# PCA9548A.net
KiCad netlist of a schematic drawn in EAGLE
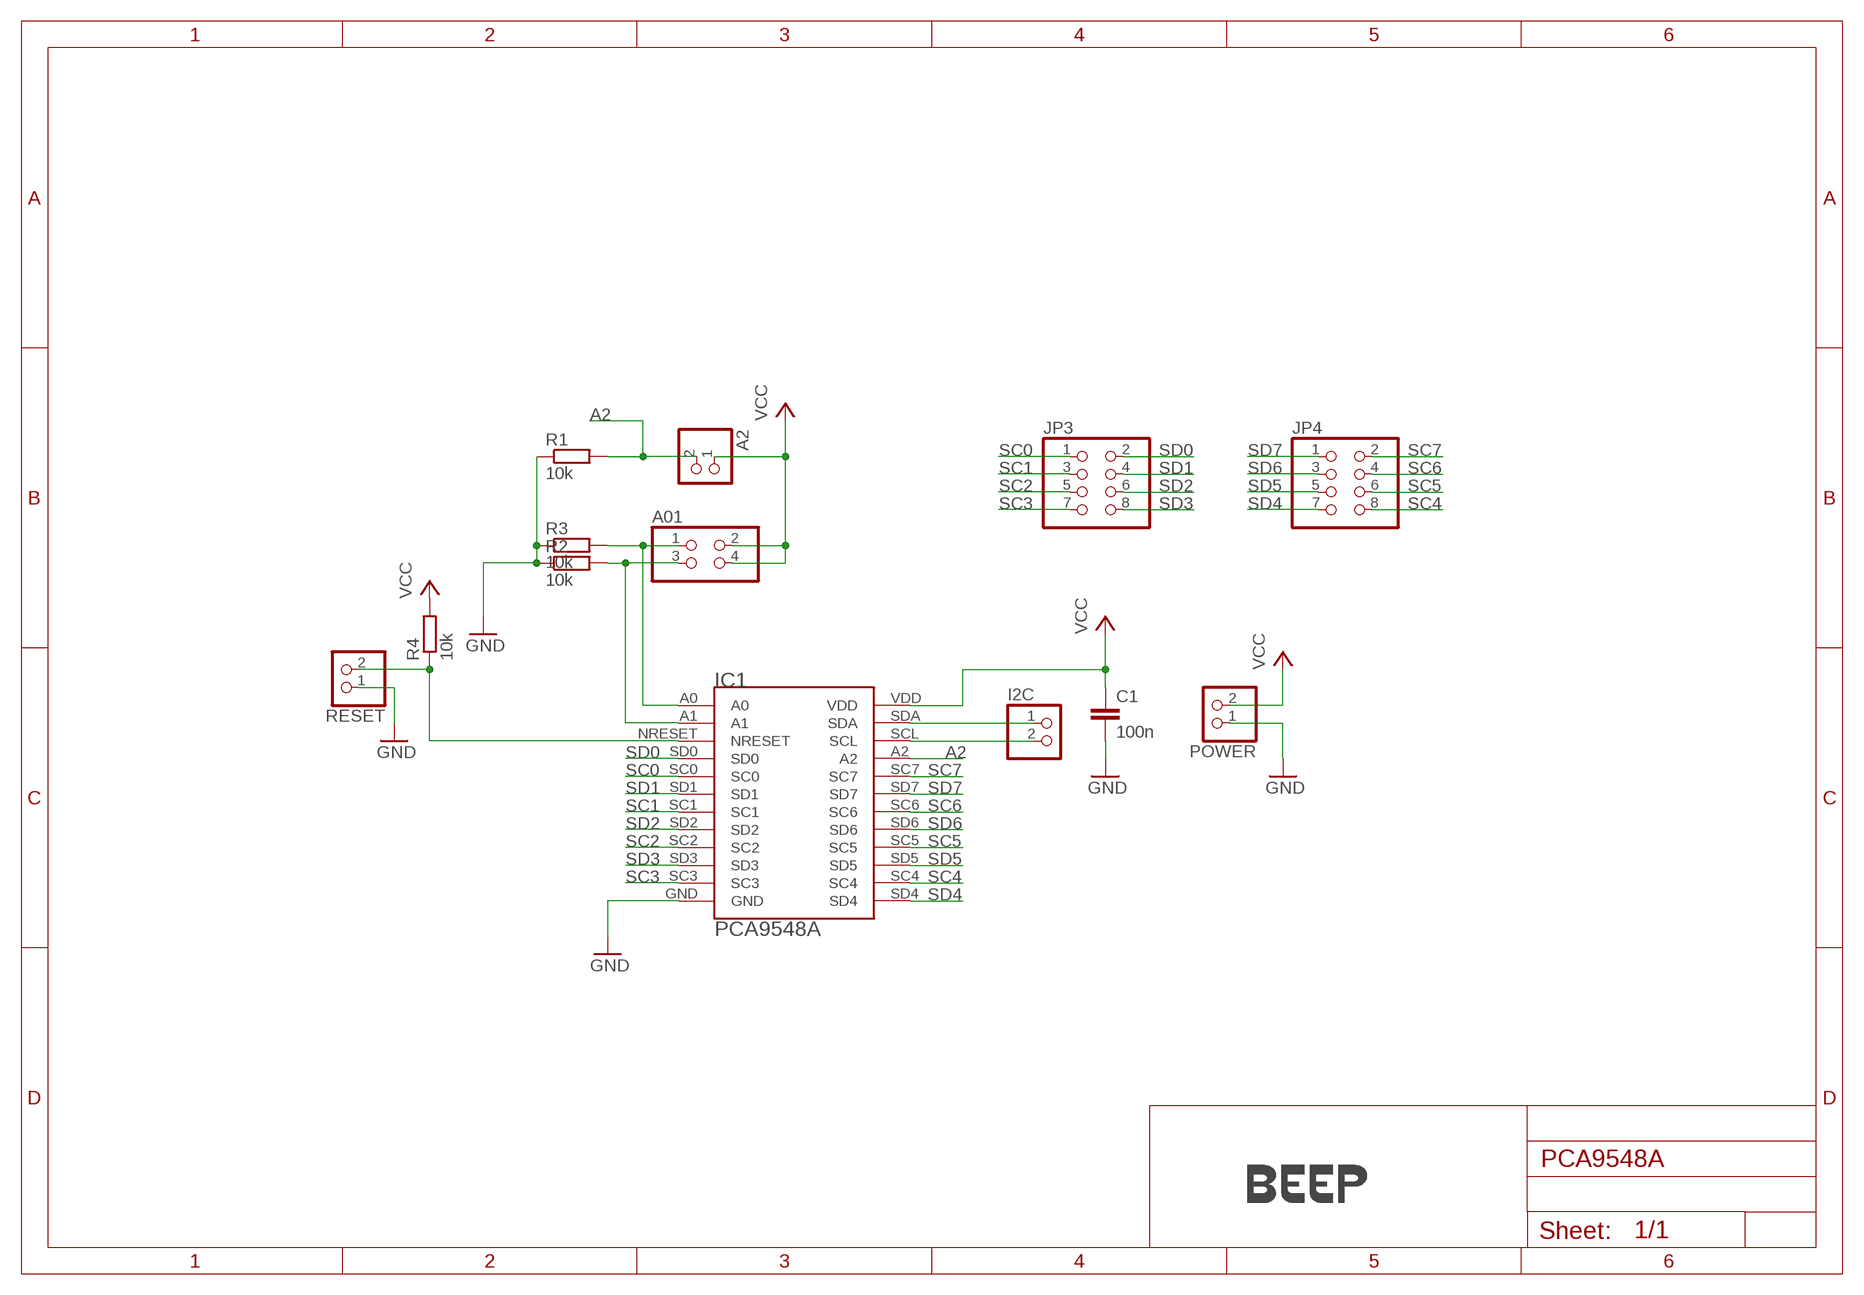
[diagram p0: schematic, sheet 1]

(export (version "E")
  (design (tool "Eeschema 10.0.6"))
  (components
    (comp (ref "A01")
      (value "PINHD-2X2")
      (footprint "eagle-import:2X02")
      (libsource (lib "eagle-import") (part "PINHD-2X2"))
    )
    (comp (ref "A2")
      (value "PINHD-1X2")
      (footprint "eagle-import:1X02")
      (libsource (lib "eagle-import") (part "PINHD-1X2"))
    )
    (comp (ref "C1")
      (value "100n")
      (footprint "eagle-import:C0805")
      (libsource (lib "eagle-import") (part "C-EUC0805"))
    )
    (comp (ref "I2C")
      (value "PINHD-1X2")
      (footprint "eagle-import:1X02")
      (libsource (lib "eagle-import") (part "PINHD-1X2"))
    )
    (comp (ref "IC1")
      (value "PCA9548A")
      (footprint "eagle-import:TSSOP24")
      (libsource (lib "eagle-import") (part "PCA9548A"))
    )
    (comp (ref "JP3")
      (value "PINHD-2X4")
      (footprint "eagle-import:2X04")
      (libsource (lib "eagle-import") (part "PINHD-2X4"))
    )
    (comp (ref "JP4")
      (value "PINHD-2X4")
      (footprint "eagle-import:2X04")
      (libsource (lib "eagle-import") (part "PINHD-2X4"))
    )
    (comp (ref "POWER")
      (value "PINHD-1X2")
      (footprint "eagle-import:1X02")
      (libsource (lib "eagle-import") (part "PINHD-1X2"))
    )
    (comp (ref "R1")
      (value "10k")
      (footprint "eagle-import:0207_7")
      (libsource (lib "eagle-import") (part "R-EU_0207/7"))
    )
    (comp (ref "R2")
      (value "10k")
      (footprint "eagle-import:0207_7")
      (libsource (lib "eagle-import") (part "R-EU_0207/7"))
    )
    (comp (ref "R3")
      (value "10k")
      (footprint "eagle-import:0207_7")
      (libsource (lib "eagle-import") (part "R-EU_0207/7"))
    )
    (comp (ref "R4")
      (value "10k")
      (footprint "eagle-import:M0805")
      (libsource (lib "eagle-import") (part "R-EU_M0805"))
    )
    (comp (ref "RESET")
      (value "PINHD-1X2")
      (footprint "eagle-import:1X02")
      (libsource (lib "eagle-import") (part "PINHD-1X2"))
    )
    (comp (ref "U$1")
      (value "LOGO-COPPER4")
      (footprint "eagle-import:COPPER4")
      (libsource (lib "eagle-import") (part "LOGO-COPPER4"))
    )
  )
  (nets
    (net (code "1") (name "/A2") (class "Default")
      (node (ref "A2") (pin "2") (pinfunction "2_2") (pintype "passive"))
      (node (ref "IC1") (pin "A2") (pinfunction "A2_A2") (pintype "bidirectional"))
      (node (ref "R1") (pin "2") (pinfunction "2_2") (pintype "passive"))
    )
    (net (code "2") (name "/SC0") (class "Default")
      (node (ref "IC1") (pin "SC0") (pinfunction "SC0_SC0") (pintype "bidirectional"))
      (node (ref "JP3") (pin "1") (pinfunction "1_1") (pintype "passive"))
    )
    (net (code "3") (name "/SC1") (class "Default")
      (node (ref "IC1") (pin "SC1") (pinfunction "SC1_SC1") (pintype "bidirectional"))
      (node (ref "JP3") (pin "3") (pinfunction "3_3") (pintype "passive"))
    )
    (net (code "4") (name "/SC2") (class "Default")
      (node (ref "IC1") (pin "SC2") (pinfunction "SC2_SC2") (pintype "bidirectional"))
      (node (ref "JP3") (pin "5") (pinfunction "5_5") (pintype "passive"))
    )
    (net (code "5") (name "/SC3") (class "Default")
      (node (ref "IC1") (pin "SC3") (pinfunction "SC3_SC3") (pintype "bidirectional"))
      (node (ref "JP3") (pin "7") (pinfunction "7_7") (pintype "passive"))
    )
    (net (code "6") (name "/SC4") (class "Default")
      (node (ref "IC1") (pin "SC4") (pinfunction "SC4_SC4") (pintype "bidirectional"))
      (node (ref "JP4") (pin "8") (pinfunction "8_8") (pintype "passive"))
    )
    (net (code "7") (name "/SC5") (class "Default")
      (node (ref "IC1") (pin "SC5") (pinfunction "SC5_SC5") (pintype "bidirectional"))
      (node (ref "JP4") (pin "6") (pinfunction "6_6") (pintype "passive"))
    )
    (net (code "8") (name "/SC6") (class "Default")
      (node (ref "IC1") (pin "SC6") (pinfunction "SC6_SC6") (pintype "bidirectional"))
      (node (ref "JP4") (pin "4") (pinfunction "4_4") (pintype "passive"))
    )
    (net (code "9") (name "/SC7") (class "Default")
      (node (ref "IC1") (pin "SC7") (pinfunction "SC7_SC7") (pintype "bidirectional"))
      (node (ref "JP4") (pin "2") (pinfunction "2_2") (pintype "passive"))
    )
    (net (code "10") (name "/SD0") (class "Default")
      (node (ref "IC1") (pin "SD0") (pinfunction "SD0_SD0") (pintype "bidirectional"))
      (node (ref "JP3") (pin "2") (pinfunction "2_2") (pintype "passive"))
    )
    (net (code "11") (name "/SD1") (class "Default")
      (node (ref "IC1") (pin "SD1") (pinfunction "SD1_SD1") (pintype "bidirectional"))
      (node (ref "JP3") (pin "4") (pinfunction "4_4") (pintype "passive"))
    )
    (net (code "12") (name "/SD2") (class "Default")
      (node (ref "IC1") (pin "SD2") (pinfunction "SD2_SD2") (pintype "bidirectional"))
      (node (ref "JP3") (pin "6") (pinfunction "6_6") (pintype "passive"))
    )
    (net (code "13") (name "/SD3") (class "Default")
      (node (ref "IC1") (pin "SD3") (pinfunction "SD3_SD3") (pintype "bidirectional"))
      (node (ref "JP3") (pin "8") (pinfunction "8_8") (pintype "passive"))
    )
    (net (code "14") (name "/SD4") (class "Default")
      (node (ref "IC1") (pin "SD4") (pinfunction "SD4_SD4") (pintype "bidirectional"))
      (node (ref "JP4") (pin "7") (pinfunction "7_7") (pintype "passive"))
    )
    (net (code "15") (name "/SD5") (class "Default")
      (node (ref "IC1") (pin "SD5") (pinfunction "SD5_SD5") (pintype "bidirectional"))
      (node (ref "JP4") (pin "5") (pinfunction "5_5") (pintype "passive"))
    )
    (net (code "16") (name "/SD6") (class "Default")
      (node (ref "IC1") (pin "SD6") (pinfunction "SD6_SD6") (pintype "bidirectional"))
      (node (ref "JP4") (pin "3") (pinfunction "3_3") (pintype "passive"))
    )
    (net (code "17") (name "/SD7") (class "Default")
      (node (ref "IC1") (pin "SD7") (pinfunction "SD7_SD7") (pintype "bidirectional"))
      (node (ref "JP4") (pin "1") (pinfunction "1_1") (pintype "passive"))
    )
    (net (code "18") (name "GND") (class "Default")
      (node (ref "C1") (pin "2") (pinfunction "2_2") (pintype "passive"))
      (node (ref "IC1") (pin "GND") (pinfunction "GND_GND") (pintype "power_in"))
      (node (ref "POWER") (pin "1") (pinfunction "1_1") (pintype "passive"))
      (node (ref "R1") (pin "1") (pinfunction "1_1") (pintype "passive"))
      (node (ref "R2") (pin "1") (pinfunction "1_1") (pintype "passive"))
      (node (ref "R3") (pin "1") (pinfunction "1_1") (pintype "passive"))
      (node (ref "RESET") (pin "1") (pinfunction "1_1") (pintype "passive"))
    )
    (net (code "19") (name "Net-(A01-Pad1)") (class "Default")
      (node (ref "A01") (pin "1") (pinfunction "1_1") (pintype "passive"))
      (node (ref "IC1") (pin "A0") (pinfunction "A0_A0") (pintype "input"))
      (node (ref "R3") (pin "2") (pinfunction "2_2") (pintype "passive"))
    )
    (net (code "20") (name "Net-(A01-Pad3)") (class "Default")
      (node (ref "A01") (pin "3") (pinfunction "3_3") (pintype "passive"))
      (node (ref "IC1") (pin "A1") (pinfunction "A1_A1") (pintype "input"))
      (node (ref "R2") (pin "2") (pinfunction "2_2") (pintype "passive"))
    )
    (net (code "21") (name "Net-(I2C-Pad1)") (class "Default")
      (node (ref "I2C") (pin "1") (pinfunction "1_1") (pintype "passive"))
      (node (ref "IC1") (pin "SDA") (pinfunction "SDA_SDA") (pintype "bidirectional"))
    )
    (net (code "22") (name "Net-(I2C-Pad2)") (class "Default")
      (node (ref "I2C") (pin "2") (pinfunction "2_2") (pintype "passive"))
      (node (ref "IC1") (pin "SCL") (pinfunction "SCL_SCL") (pintype "bidirectional"))
    )
    (net (code "23") (name "Net-(IC1-PadNRESET)") (class "Default")
      (node (ref "IC1") (pin "NRESET") (pinfunction "NRESET_NRESET") (pintype "input"))
      (node (ref "R4") (pin "1") (pinfunction "1_1") (pintype "passive"))
      (node (ref "RESET") (pin "2") (pinfunction "2_2") (pintype "passive"))
    )
    (net (code "24") (name "VCC") (class "Default")
      (node (ref "A01") (pin "2") (pinfunction "2_2") (pintype "passive"))
      (node (ref "A01") (pin "4") (pinfunction "4_4") (pintype "passive"))
      (node (ref "A2") (pin "1") (pinfunction "1_1") (pintype "passive"))
      (node (ref "C1") (pin "1") (pinfunction "1_1") (pintype "passive"))
      (node (ref "IC1") (pin "VDD") (pinfunction "VDD_VDD") (pintype "power_in"))
      (node (ref "POWER") (pin "2") (pinfunction "2_2") (pintype "passive"))
      (node (ref "R4") (pin "2") (pinfunction "2_2") (pintype "passive"))
    )
  )
)
